# voice-card-controller-1_1.net
KiCad netlist of a schematic drawn in EAGLE
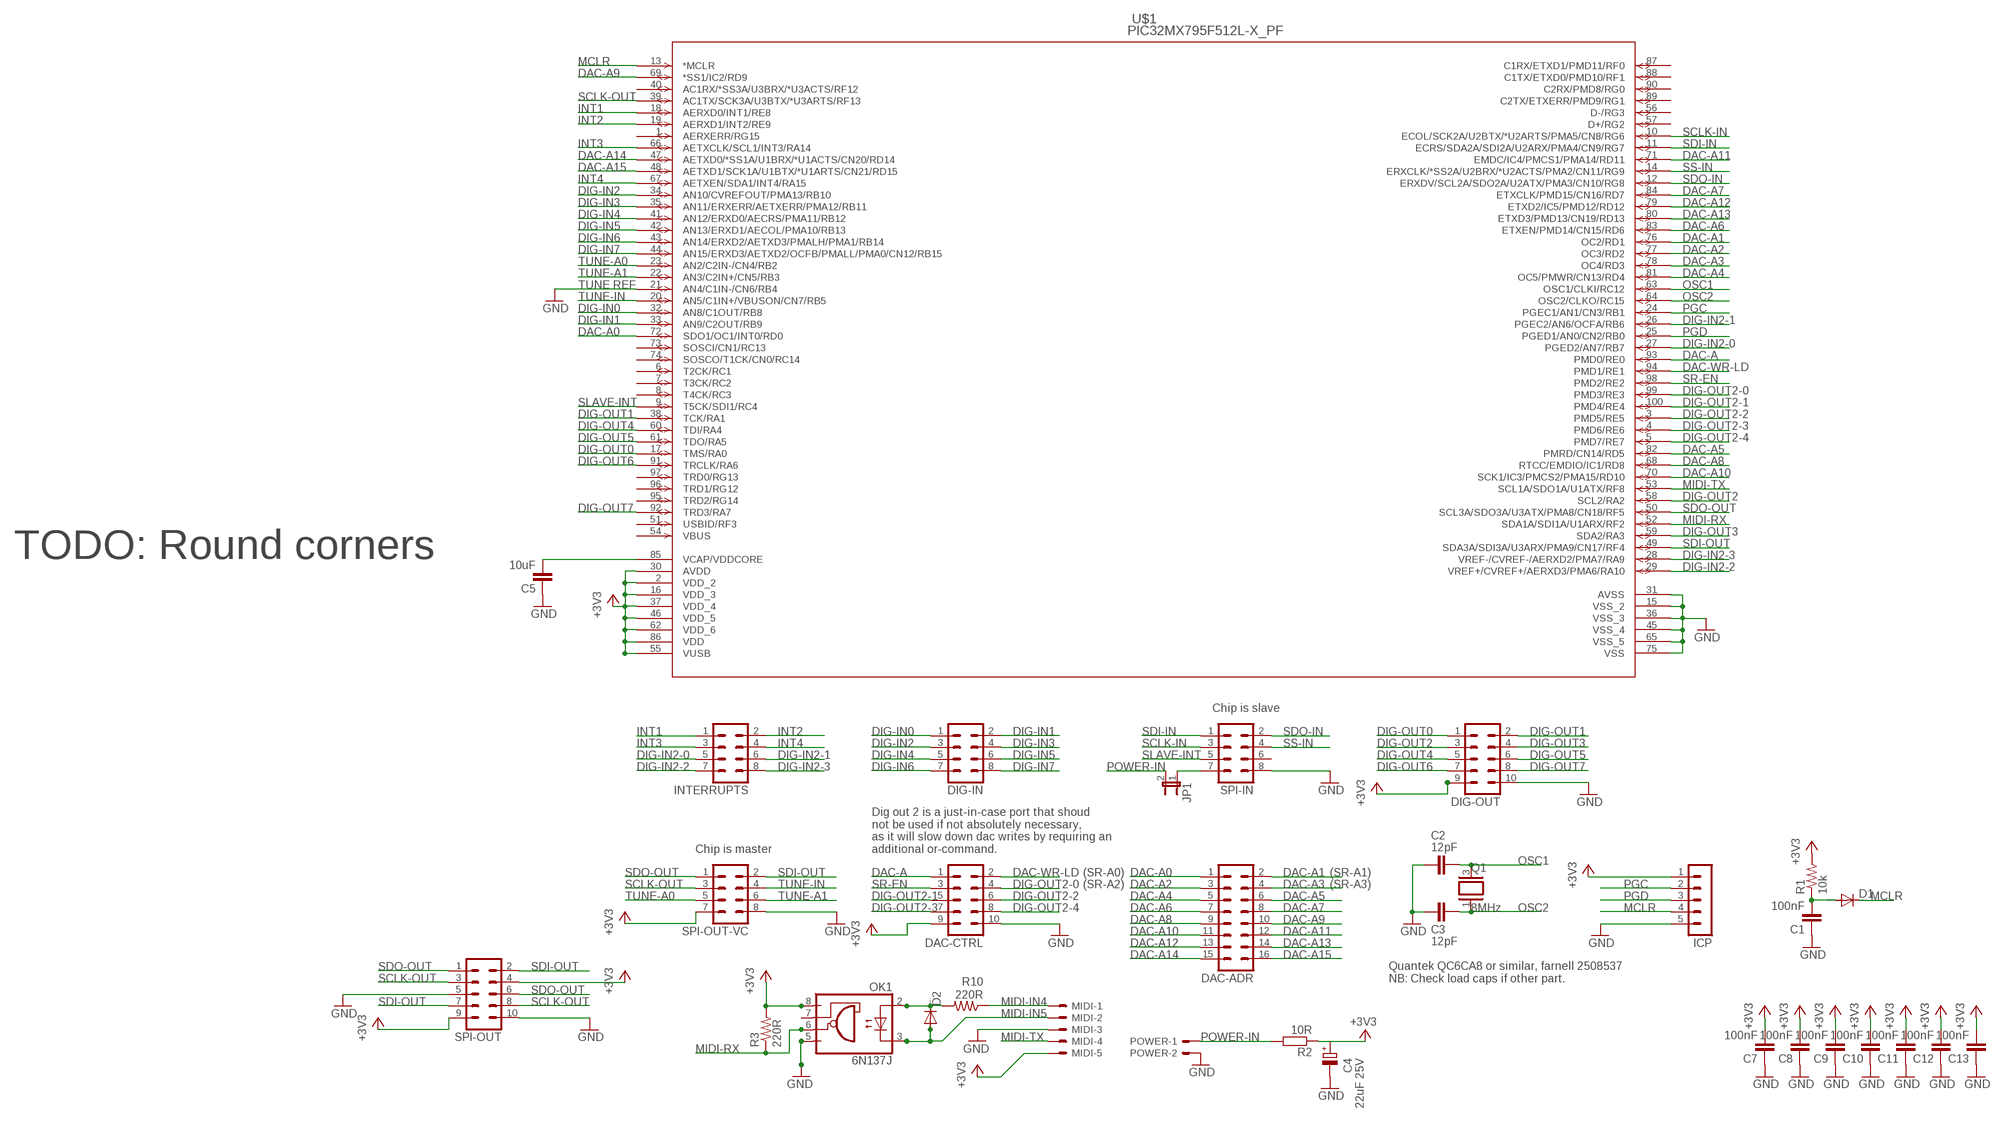
[diagram p0: schematic, sheet 1]

(export (version "E")
  (design (tool "Eeschema 10.0.6"))
  (components
    (comp (ref "C1")
      (value "100nF")
      (footprint "eagle-import:C0603")
      (libsource (lib "eagle-import") (part "C-EUC0603"))
    )
    (comp (ref "C2")
      (value "12pF")
      (footprint "eagle-import:C0603")
      (libsource (lib "eagle-import") (part "C-EUC0603"))
    )
    (comp (ref "C3")
      (value "12pF")
      (footprint "eagle-import:C0603")
      (libsource (lib "eagle-import") (part "C-EUC0603"))
    )
    (comp (ref "C4")
      (value "22uF 25V")
      (footprint "eagle-import:E2,5-5")
      (libsource (lib "eagle-import") (part "CPOL-EUE2.5-5"))
    )
    (comp (ref "C5")
      (value "10uF")
      (footprint "eagle-import:C0805")
      (libsource (lib "eagle-import") (part "C-EUC0805"))
    )
    (comp (ref "C7")
      (value "100nF")
      (footprint "eagle-import:C0603")
      (libsource (lib "eagle-import") (part "C-EUC0603"))
    )
    (comp (ref "C8")
      (value "100nF")
      (footprint "eagle-import:C0603")
      (libsource (lib "eagle-import") (part "C-EUC0603"))
    )
    (comp (ref "C9")
      (value "100nF")
      (footprint "eagle-import:C0603")
      (libsource (lib "eagle-import") (part "C-EUC0603"))
    )
    (comp (ref "C10")
      (value "100nF")
      (footprint "eagle-import:C0603")
      (libsource (lib "eagle-import") (part "C-EUC0603"))
    )
    (comp (ref "C11")
      (value "100nF")
      (footprint "eagle-import:C0603")
      (libsource (lib "eagle-import") (part "C-EUC0603"))
    )
    (comp (ref "C12")
      (value "100nF")
      (footprint "eagle-import:C0603")
      (libsource (lib "eagle-import") (part "C-EUC0603"))
    )
    (comp (ref "C13")
      (value "100nF")
      (footprint "eagle-import:C0603")
      (libsource (lib "eagle-import") (part "C-EUC0603"))
    )
    (comp (ref "D1")
      (value "DIODE-SOD80C")
      (footprint "eagle-import:SOD80C")
      (libsource (lib "eagle-import") (part "DIODE-SOD80C"))
    )
    (comp (ref "D2")
      (value "DIODE-SOD80C")
      (footprint "eagle-import:SOD80C")
      (libsource (lib "eagle-import") (part "DIODE-SOD80C"))
    )
    (comp (ref "DAC-ADR")
      (value "MA08-2J")
      (footprint "eagle-import:MA08-2J")
      (libsource (lib "eagle-import") (part "MA08-2J"))
    )
    (comp (ref "DAC-CTRL")
      (value "MA05-2J")
      (footprint "eagle-import:MA05-2J")
      (libsource (lib "eagle-import") (part "MA05-2J"))
    )
    (comp (ref "DIG-IN")
      (value "MA04-2J")
      (footprint "eagle-import:MA04-2J")
      (libsource (lib "eagle-import") (part "MA04-2J"))
    )
    (comp (ref "DIG-OUT")
      (value "MA05-2J")
      (footprint "eagle-import:MA05-2J")
      (libsource (lib "eagle-import") (part "MA05-2J"))
    )
    (comp (ref "ICP")
      (value "MA05-1")
      (footprint "eagle-import:MA05-1")
      (libsource (lib "eagle-import") (part "MA05-1"))
    )
    (comp (ref "INTERRUPTS")
      (value "MA04-2J")
      (footprint "eagle-import:MA04-2J")
      (libsource (lib "eagle-import") (part "MA04-2J"))
    )
    (comp (ref "JP1")
      (value "JP1E")
      (footprint "eagle-import:JP1")
      (libsource (lib "eagle-import") (part "JP1E"))
    )
    (comp (ref "MIDI")
      (value "22-23-2051")
      (footprint "eagle-import:22-23-2051")
      (fields (field (name "MF") "MOLEX"))
      (libsource (lib "eagle-import") (part "22-23-2051"))
    )
    (comp (ref "OK1")
      (value "6N137J")
      (footprint "eagle-import:DIL08-J")
      (libsource (lib "eagle-import") (part "6N137J"))
    )
    (comp (ref "POWER")
      (value "22-23-2021")
      (footprint "eagle-import:22-23-2021")
      (fields (field (name "MF") "MOLEX"))
      (libsource (lib "eagle-import") (part "22-23-2021"))
    )
    (comp (ref "Q1")
      (value "8MHz")
      (footprint "eagle-import:CTS406J")
      (libsource (lib "eagle-import") (part "XTAL-J"))
    )
    (comp (ref "R1")
      (value "10k")
      (footprint "eagle-import:R0805")
      (libsource (lib "eagle-import") (part "R-US_R0805"))
    )
    (comp (ref "R2")
      (value "10R")
      (footprint "eagle-import:0207_7")
      (libsource (lib "eagle-import") (part "R-EU_0207/7"))
    )
    (comp (ref "R3")
      (value "220R")
      (footprint "eagle-import:R0805")
      (libsource (lib "eagle-import") (part "R-US_R0805"))
    )
    (comp (ref "R10")
      (value "220R")
      (footprint "eagle-import:R0805")
      (libsource (lib "eagle-import") (part "R-US_R0805"))
    )
    (comp (ref "SPI-IN")
      (value "MA04-2J")
      (footprint "eagle-import:MA04-2J")
      (libsource (lib "eagle-import") (part "MA04-2J"))
    )
    (comp (ref "SPI-OUT")
      (value "MA05-2J")
      (footprint "eagle-import:MA05-2J")
      (libsource (lib "eagle-import") (part "MA05-2J"))
    )
    (comp (ref "SPI-OUT-VC")
      (value "MA04-2J")
      (footprint "eagle-import:MA04-2J")
      (libsource (lib "eagle-import") (part "MA04-2J"))
    )
    (comp (ref "U$1")
      (value "PIC32MX795F512L-X_PF")
      (footprint "eagle-import:TQFP100_14X14MC")
      (libsource (lib "eagle-import") (part "PIC32MX795F512L-X_PF"))
    )
  )
  (nets
    (net (code "1") (name "+3V3") (class "Default")
      (node (ref "C10") (pin "2") (pinfunction "2_2") (pintype "passive"))
      (node (ref "C11") (pin "2") (pinfunction "2_2") (pintype "passive"))
      (node (ref "C12") (pin "2") (pinfunction "2_2") (pintype "passive"))
      (node (ref "C13") (pin "2") (pinfunction "2_2") (pintype "passive"))
      (node (ref "C4") (pin "+") (pinfunction "+_+") (pintype "passive"))
      (node (ref "C7") (pin "2") (pinfunction "2_2") (pintype "passive"))
      (node (ref "C8") (pin "2") (pinfunction "2_2") (pintype "passive"))
      (node (ref "C9") (pin "2") (pinfunction "2_2") (pintype "passive"))
      (node (ref "DAC-CTRL") (pin "9") (pinfunction "9_9") (pintype "passive"))
      (node (ref "DIG-OUT") (pin "9") (pinfunction "9_9") (pintype "passive"))
      (node (ref "ICP") (pin "1") (pinfunction "1_1") (pintype "passive"))
      (node (ref "MIDI") (pin "5") (pinfunction "S_5") (pintype "passive"))
      (node (ref "OK1") (pin "8") (pinfunction "VCC_8") (pintype "passive"))
      (node (ref "R1") (pin "2") (pinfunction "2_2") (pintype "passive"))
      (node (ref "R2") (pin "1") (pinfunction "1_1") (pintype "passive"))
      (node (ref "R3") (pin "2") (pinfunction "2_2") (pintype "passive"))
      (node (ref "SPI-OUT") (pin "4") (pinfunction "4_4") (pintype "passive"))
      (node (ref "SPI-OUT") (pin "9") (pinfunction "9_9") (pintype "passive"))
      (node (ref "SPI-OUT-VC") (pin "7") (pinfunction "7_7") (pintype "passive"))
      (node (ref "U$1") (pin "16") (pinfunction "VDD_3_16") (pintype "power_in"))
      (node (ref "U$1") (pin "2") (pinfunction "VDD_2_2") (pintype "power_in"))
      (node (ref "U$1") (pin "30") (pinfunction "AVDD_30") (pintype "power_in"))
      (node (ref "U$1") (pin "37") (pinfunction "VDD_4_37") (pintype "power_in"))
      (node (ref "U$1") (pin "46") (pinfunction "VDD_5_46") (pintype "power_in"))
      (node (ref "U$1") (pin "55") (pinfunction "VUSB_55") (pintype "power_in"))
      (node (ref "U$1") (pin "62") (pinfunction "VDD_6_62") (pintype "power_in"))
      (node (ref "U$1") (pin "86") (pinfunction "VDD_86") (pintype "power_in"))
    )
    (net (code "2") (name "/DAC-A") (class "Default")
      (node (ref "DAC-CTRL") (pin "1") (pinfunction "1_1") (pintype "passive"))
      (node (ref "U$1") (pin "93") (pinfunction "PMD0/RE0_93") (pintype "bidirectional"))
    )
    (net (code "3") (name "/DAC-A0") (class "Default")
      (node (ref "DAC-ADR") (pin "1") (pinfunction "1_1") (pintype "passive"))
      (node (ref "U$1") (pin "72") (pinfunction "SDO1/OC1/INT0/RD0_72") (pintype "bidirectional"))
    )
    (net (code "4") (name "/DAC-A1") (class "Default")
      (node (ref "DAC-ADR") (pin "2") (pinfunction "2_2") (pintype "passive"))
      (node (ref "U$1") (pin "76") (pinfunction "OC2/RD1_76") (pintype "bidirectional"))
    )
    (net (code "5") (name "/DAC-A2") (class "Default")
      (node (ref "DAC-ADR") (pin "3") (pinfunction "3_3") (pintype "passive"))
      (node (ref "U$1") (pin "77") (pinfunction "OC3/RD2_77") (pintype "bidirectional"))
    )
    (net (code "6") (name "/DAC-A3") (class "Default")
      (node (ref "DAC-ADR") (pin "4") (pinfunction "4_4") (pintype "passive"))
      (node (ref "U$1") (pin "78") (pinfunction "OC4/RD3_78") (pintype "bidirectional"))
    )
    (net (code "7") (name "/DAC-A4") (class "Default")
      (node (ref "DAC-ADR") (pin "5") (pinfunction "5_5") (pintype "passive"))
      (node (ref "U$1") (pin "81") (pinfunction "OC5/PMWR/CN13/RD4_81") (pintype "bidirectional"))
    )
    (net (code "8") (name "/DAC-A5") (class "Default")
      (node (ref "DAC-ADR") (pin "6") (pinfunction "6_6") (pintype "passive"))
      (node (ref "U$1") (pin "82") (pinfunction "PMRD/CN14/RD5_82") (pintype "bidirectional"))
    )
    (net (code "9") (name "/DAC-A6") (class "Default")
      (node (ref "DAC-ADR") (pin "7") (pinfunction "7_7") (pintype "passive"))
      (node (ref "U$1") (pin "83") (pinfunction "ETXEN/PMD14/CN15/RD6_83") (pintype "bidirectional"))
    )
    (net (code "10") (name "/DAC-A7") (class "Default")
      (node (ref "DAC-ADR") (pin "8") (pinfunction "8_8") (pintype "passive"))
      (node (ref "U$1") (pin "84") (pinfunction "ETXCLK/PMD15/CN16/RD7_84") (pintype "bidirectional"))
    )
    (net (code "11") (name "/DAC-A8") (class "Default")
      (node (ref "DAC-ADR") (pin "9") (pinfunction "9_9") (pintype "passive"))
      (node (ref "U$1") (pin "68") (pinfunction "RTCC/EMDIO/IC1/RD8_68") (pintype "bidirectional"))
    )
    (net (code "12") (name "/DAC-A9") (class "Default")
      (node (ref "DAC-ADR") (pin "10") (pinfunction "10_10") (pintype "passive"))
      (node (ref "U$1") (pin "69") (pinfunction "*SS1/IC2/RD9_69") (pintype "bidirectional"))
    )
    (net (code "13") (name "/DAC-A10") (class "Default")
      (node (ref "DAC-ADR") (pin "11") (pinfunction "11_11") (pintype "passive"))
      (node (ref "U$1") (pin "70") (pinfunction "SCK1/IC3/PMCS2/PMA15/RD10_70") (pintype "bidirectional"))
    )
    (net (code "14") (name "/DAC-A11") (class "Default")
      (node (ref "DAC-ADR") (pin "12") (pinfunction "12_12") (pintype "passive"))
      (node (ref "U$1") (pin "71") (pinfunction "EMDC/IC4/PMCS1/PMA14/RD11_71") (pintype "bidirectional"))
    )
    (net (code "15") (name "/DAC-A12") (class "Default")
      (node (ref "DAC-ADR") (pin "13") (pinfunction "13_13") (pintype "passive"))
      (node (ref "U$1") (pin "79") (pinfunction "ETXD2/IC5/PMD12/RD12_79") (pintype "bidirectional"))
    )
    (net (code "16") (name "/DAC-A13") (class "Default")
      (node (ref "DAC-ADR") (pin "14") (pinfunction "14_14") (pintype "passive"))
      (node (ref "U$1") (pin "80") (pinfunction "ETXD3/PMD13/CN19/RD13_80") (pintype "bidirectional"))
    )
    (net (code "17") (name "/DAC-A14") (class "Default")
      (node (ref "DAC-ADR") (pin "15") (pinfunction "15_15") (pintype "passive"))
      (node (ref "U$1") (pin "47") (pinfunction "AETXD0/*SS1A/U1BRX/*U1ACTS/CN20/RD14_47") (pintype "bidirectional"))
    )
    (net (code "18") (name "/DAC-A15") (class "Default")
      (node (ref "DAC-ADR") (pin "16") (pinfunction "16_16") (pintype "passive"))
      (node (ref "U$1") (pin "48") (pinfunction "AETXD1/SCK1A/U1BTX/*U1ARTS/CN21/RD15_48") (pintype "bidirectional"))
    )
    (net (code "19") (name "/DAC-WR-LD") (class "Default")
      (node (ref "DAC-CTRL") (pin "2") (pinfunction "2_2") (pintype "passive"))
      (node (ref "U$1") (pin "94") (pinfunction "PMD1/RE1_94") (pintype "bidirectional"))
    )
    (net (code "20") (name "/DIG-IN0") (class "Default")
      (node (ref "DIG-IN") (pin "1") (pinfunction "1_1") (pintype "passive"))
      (node (ref "U$1") (pin "32") (pinfunction "AN8/C1OUT/RB8_32") (pintype "bidirectional"))
    )
    (net (code "21") (name "/DIG-IN1") (class "Default")
      (node (ref "DIG-IN") (pin "2") (pinfunction "2_2") (pintype "passive"))
      (node (ref "U$1") (pin "33") (pinfunction "AN9/C2OUT/RB9_33") (pintype "bidirectional"))
    )
    (net (code "22") (name "/DIG-IN2") (class "Default")
      (node (ref "DIG-IN") (pin "3") (pinfunction "3_3") (pintype "passive"))
      (node (ref "U$1") (pin "34") (pinfunction "AN10/CVREFOUT/PMA13/RB10_34") (pintype "bidirectional"))
    )
    (net (code "23") (name "/DIG-IN2-0") (class "Default")
      (node (ref "INTERRUPTS") (pin "5") (pinfunction "5_5") (pintype "passive"))
      (node (ref "U$1") (pin "27") (pinfunction "PGED2/AN7/RB7_27") (pintype "bidirectional"))
    )
    (net (code "24") (name "/DIG-IN2-1") (class "Default")
      (node (ref "INTERRUPTS") (pin "6") (pinfunction "6_6") (pintype "passive"))
      (node (ref "U$1") (pin "26") (pinfunction "PGEC2/AN6/OCFA/RB6_26") (pintype "bidirectional"))
    )
    (net (code "25") (name "/DIG-IN2-2") (class "Default")
      (node (ref "INTERRUPTS") (pin "7") (pinfunction "7_7") (pintype "passive"))
      (node (ref "U$1") (pin "29") (pinfunction "VREF+/CVREF+/AERXD3/PMA6/RA10_29") (pintype "bidirectional"))
    )
    (net (code "26") (name "/DIG-IN2-3") (class "Default")
      (node (ref "INTERRUPTS") (pin "8") (pinfunction "8_8") (pintype "passive"))
      (node (ref "U$1") (pin "28") (pinfunction "VREF-/CVREF-/AERXD2/PMA7/RA9_28") (pintype "bidirectional"))
    )
    (net (code "27") (name "/DIG-IN3") (class "Default")
      (node (ref "DIG-IN") (pin "4") (pinfunction "4_4") (pintype "passive"))
      (node (ref "U$1") (pin "35") (pinfunction "AN11/ERXERR/AETXERR/PMA12/RB11_35") (pintype "bidirectional"))
    )
    (net (code "28") (name "/DIG-IN4") (class "Default")
      (node (ref "DIG-IN") (pin "5") (pinfunction "5_5") (pintype "passive"))
      (node (ref "U$1") (pin "41") (pinfunction "AN12/ERXD0/AECRS/PMA11/RB12_41") (pintype "bidirectional"))
    )
    (net (code "29") (name "/DIG-IN5") (class "Default")
      (node (ref "DIG-IN") (pin "6") (pinfunction "6_6") (pintype "passive"))
      (node (ref "U$1") (pin "42") (pinfunction "AN13/ERXD1/AECOL/PMA10/RB13_42") (pintype "bidirectional"))
    )
    (net (code "30") (name "/DIG-IN6") (class "Default")
      (node (ref "DIG-IN") (pin "7") (pinfunction "7_7") (pintype "passive"))
      (node (ref "U$1") (pin "43") (pinfunction "AN14/ERXD2/AETXD3/PMALH/PMA1/RB14_43") (pintype "bidirectional"))
    )
    (net (code "31") (name "/DIG-IN7") (class "Default")
      (node (ref "DIG-IN") (pin "8") (pinfunction "8_8") (pintype "passive"))
      (node (ref "U$1") (pin "44") (pinfunction "AN15/ERXD3/AETXD2/OCFB/PMALL/PMA0/CN12/RB15_44") (pintype "bidirectional"))
    )
    (net (code "32") (name "/DIG-OUT0") (class "Default")
      (node (ref "DIG-OUT") (pin "1") (pinfunction "1_1") (pintype "passive"))
      (node (ref "U$1") (pin "17") (pinfunction "TMS/RA0_17") (pintype "bidirectional"))
    )
    (net (code "33") (name "/DIG-OUT1") (class "Default")
      (node (ref "DIG-OUT") (pin "2") (pinfunction "2_2") (pintype "passive"))
      (node (ref "U$1") (pin "38") (pinfunction "TCK/RA1_38") (pintype "bidirectional"))
    )
    (net (code "34") (name "/DIG-OUT2") (class "Default")
      (node (ref "DIG-OUT") (pin "3") (pinfunction "3_3") (pintype "passive"))
      (node (ref "U$1") (pin "58") (pinfunction "SCL2/RA2_58") (pintype "bidirectional"))
    )
    (net (code "35") (name "/DIG-OUT2-0") (class "Default")
      (node (ref "DAC-CTRL") (pin "4") (pinfunction "4_4") (pintype "passive"))
      (node (ref "U$1") (pin "99") (pinfunction "PMD3/RE3_99") (pintype "bidirectional"))
    )
    (net (code "36") (name "/DIG-OUT2-1") (class "Default")
      (node (ref "DAC-CTRL") (pin "5") (pinfunction "5_5") (pintype "passive"))
      (node (ref "U$1") (pin "100") (pinfunction "PMD4/RE4_100") (pintype "bidirectional"))
    )
    (net (code "37") (name "/DIG-OUT2-2") (class "Default")
      (node (ref "DAC-CTRL") (pin "6") (pinfunction "6_6") (pintype "passive"))
      (node (ref "U$1") (pin "3") (pinfunction "PMD5/RE5_3") (pintype "bidirectional"))
    )
    (net (code "38") (name "/DIG-OUT2-3") (class "Default")
      (node (ref "DAC-CTRL") (pin "7") (pinfunction "7_7") (pintype "passive"))
      (node (ref "U$1") (pin "4") (pinfunction "PMD6/RE6_4") (pintype "bidirectional"))
    )
    (net (code "39") (name "/DIG-OUT2-4") (class "Default")
      (node (ref "DAC-CTRL") (pin "8") (pinfunction "8_8") (pintype "passive"))
      (node (ref "U$1") (pin "5") (pinfunction "PMD7/RE7_5") (pintype "bidirectional"))
    )
    (net (code "40") (name "/DIG-OUT3") (class "Default")
      (node (ref "DIG-OUT") (pin "4") (pinfunction "4_4") (pintype "passive"))
      (node (ref "U$1") (pin "59") (pinfunction "SDA2/RA3_59") (pintype "bidirectional"))
    )
    (net (code "41") (name "/DIG-OUT4") (class "Default")
      (node (ref "DIG-OUT") (pin "5") (pinfunction "5_5") (pintype "passive"))
      (node (ref "U$1") (pin "60") (pinfunction "TDI/RA4_60") (pintype "bidirectional"))
    )
    (net (code "42") (name "/DIG-OUT5") (class "Default")
      (node (ref "DIG-OUT") (pin "6") (pinfunction "6_6") (pintype "passive"))
      (node (ref "U$1") (pin "61") (pinfunction "TDO/RA5_61") (pintype "bidirectional"))
    )
    (net (code "43") (name "/DIG-OUT6") (class "Default")
      (node (ref "DIG-OUT") (pin "7") (pinfunction "7_7") (pintype "passive"))
      (node (ref "U$1") (pin "91") (pinfunction "TRCLK/RA6_91") (pintype "bidirectional"))
    )
    (net (code "44") (name "/DIG-OUT7") (class "Default")
      (node (ref "DIG-OUT") (pin "8") (pinfunction "8_8") (pintype "passive"))
      (node (ref "U$1") (pin "92") (pinfunction "TRD3/RA7_92") (pintype "bidirectional"))
    )
    (net (code "45") (name "/INT1") (class "Default")
      (node (ref "INTERRUPTS") (pin "1") (pinfunction "1_1") (pintype "passive"))
      (node (ref "U$1") (pin "18") (pinfunction "AERXD0/INT1/RE8_18") (pintype "bidirectional"))
    )
    (net (code "46") (name "/INT2") (class "Default")
      (node (ref "INTERRUPTS") (pin "2") (pinfunction "2_2") (pintype "passive"))
      (node (ref "U$1") (pin "19") (pinfunction "AERXD1/INT2/RE9_19") (pintype "bidirectional"))
    )
    (net (code "47") (name "/INT3") (class "Default")
      (node (ref "INTERRUPTS") (pin "3") (pinfunction "3_3") (pintype "passive"))
      (node (ref "U$1") (pin "66") (pinfunction "AETXCLK/SCL1/INT3/RA14_66") (pintype "bidirectional"))
    )
    (net (code "48") (name "/INT4") (class "Default")
      (node (ref "INTERRUPTS") (pin "4") (pinfunction "4_4") (pintype "passive"))
      (node (ref "U$1") (pin "67") (pinfunction "AETXEN/SDA1/INT4/RA15_67") (pintype "bidirectional"))
    )
    (net (code "49") (name "/MCLR") (class "Default")
      (node (ref "D1") (pin "C") (pinfunction "C_C") (pintype "passive"))
      (node (ref "ICP") (pin "4") (pinfunction "4_4") (pintype "passive"))
      (node (ref "U$1") (pin "13") (pinfunction "*MCLR_13") (pintype "input"))
    )
    (net (code "50") (name "/MIDI-IN4") (class "Default")
      (node (ref "MIDI") (pin "1") (pinfunction "S_1") (pintype "passive"))
      (node (ref "R10") (pin "1") (pinfunction "1_1") (pintype "passive"))
    )
    (net (code "51") (name "/MIDI-IN5") (class "Default")
      (node (ref "D2") (pin "A") (pinfunction "A_A") (pintype "passive"))
      (node (ref "MIDI") (pin "2") (pinfunction "S_2") (pintype "passive"))
      (node (ref "OK1") (pin "3") (pinfunction "C_3") (pintype "passive"))
    )
    (net (code "52") (name "/MIDI-RX") (class "Default")
      (node (ref "OK1") (pin "6") (pinfunction "VO_6") (pintype "passive"))
      (node (ref "R3") (pin "1") (pinfunction "1_1") (pintype "passive"))
      (node (ref "U$1") (pin "52") (pinfunction "SDA1A/SDI1A/U1ARX/RF2_52") (pintype "bidirectional"))
    )
    (net (code "53") (name "/MIDI-TX") (class "Default")
      (node (ref "MIDI") (pin "4") (pinfunction "S_4") (pintype "passive"))
      (node (ref "U$1") (pin "53") (pinfunction "SCL1A/SDO1A/U1ATX/RF8_53") (pintype "bidirectional"))
    )
    (net (code "54") (name "/OSC1") (class "Default")
      (node (ref "C2") (pin "1") (pinfunction "1_1") (pintype "passive"))
      (node (ref "Q1") (pin "3") (pinfunction "2_3") (pintype "passive"))
      (node (ref "U$1") (pin "63") (pinfunction "OSC1/CLKI/RC12_63") (pintype "bidirectional"))
    )
    (net (code "55") (name "/OSC2") (class "Default")
      (node (ref "C3") (pin "1") (pinfunction "1_1") (pintype "passive"))
      (node (ref "Q1") (pin "1") (pinfunction "1_1") (pintype "passive"))
      (node (ref "U$1") (pin "64") (pinfunction "OSC2/CLKO/RC15_64") (pintype "bidirectional"))
    )
    (net (code "56") (name "/PGC") (class "Default")
      (node (ref "ICP") (pin "2") (pinfunction "2_2") (pintype "passive"))
      (node (ref "U$1") (pin "24") (pinfunction "PGEC1/AN1/CN3/RB1_24") (pintype "bidirectional"))
    )
    (net (code "57") (name "/PGD") (class "Default")
      (node (ref "ICP") (pin "3") (pinfunction "3_3") (pintype "passive"))
      (node (ref "U$1") (pin "25") (pinfunction "PGED1/AN0/CN2/RB0_25") (pintype "bidirectional"))
    )
    (net (code "58") (name "/POWER-IN") (class "Default")
      (node (ref "JP1") (pin "2") (pinfunction "2_2") (pintype "passive"))
      (node (ref "POWER") (pin "1") (pinfunction "S_1") (pintype "passive"))
      (node (ref "R2") (pin "2") (pinfunction "2_2") (pintype "passive"))
    )
    (net (code "59") (name "/SCLK-IN") (class "Default")
      (node (ref "SPI-IN") (pin "3") (pinfunction "3_3") (pintype "passive"))
      (node (ref "U$1") (pin "10") (pinfunction "ECOL/SCK2A/U2BTX/*U2ARTS/PMA5/CN8/RG6_10") (pintype "bidirectional"))
    )
    (net (code "60") (name "/SCLK-OUT") (class "Default")
      (node (ref "SPI-OUT") (pin "3") (pinfunction "3_3") (pintype "passive"))
      (node (ref "SPI-OUT") (pin "8") (pinfunction "8_8") (pintype "passive"))
      (node (ref "SPI-OUT-VC") (pin "3") (pinfunction "3_3") (pintype "passive"))
      (node (ref "U$1") (pin "39") (pinfunction "AC1TX/SCK3A/U3BTX/*U3ARTS/RF13_39") (pintype "bidirectional"))
    )
    (net (code "61") (name "/SDI-IN") (class "Default")
      (node (ref "SPI-IN") (pin "1") (pinfunction "1_1") (pintype "passive"))
      (node (ref "U$1") (pin "11") (pinfunction "ECRS/SDA2A/SDI2A/U2ARX/PMA4/CN9/RG7_11") (pintype "bidirectional"))
    )
    (net (code "62") (name "/SDI-OUT") (class "Default")
      (node (ref "SPI-OUT") (pin "2") (pinfunction "2_2") (pintype "passive"))
      (node (ref "SPI-OUT") (pin "7") (pinfunction "7_7") (pintype "passive"))
      (node (ref "SPI-OUT-VC") (pin "2") (pinfunction "2_2") (pintype "passive"))
      (node (ref "U$1") (pin "49") (pinfunction "SDA3A/SDI3A/U3ARX/PMA9/CN17/RF4_49") (pintype "bidirectional"))
    )
    (net (code "63") (name "/SDO-IN") (class "Default")
      (node (ref "SPI-IN") (pin "2") (pinfunction "2_2") (pintype "passive"))
      (node (ref "U$1") (pin "12") (pinfunction "ERXDV/SCL2A/SDO2A/U2ATX/PMA3/CN10/RG8_12") (pintype "bidirectional"))
    )
    (net (code "64") (name "/SDO-OUT") (class "Default")
      (node (ref "SPI-OUT") (pin "1") (pinfunction "1_1") (pintype "passive"))
      (node (ref "SPI-OUT") (pin "6") (pinfunction "6_6") (pintype "passive"))
      (node (ref "SPI-OUT-VC") (pin "1") (pinfunction "1_1") (pintype "passive"))
      (node (ref "U$1") (pin "50") (pinfunction "SCL3A/SDO3A/U3ATX/PMA8/CN18/RF5_50") (pintype "bidirectional"))
    )
    (net (code "65") (name "/SLAVE-INT") (class "Default")
      (node (ref "SPI-IN") (pin "5") (pinfunction "5_5") (pintype "passive"))
      (node (ref "U$1") (pin "9") (pinfunction "T5CK/SDI1/RC4_9") (pintype "bidirectional"))
    )
    (net (code "66") (name "/SR-EN") (class "Default")
      (node (ref "DAC-CTRL") (pin "3") (pinfunction "3_3") (pintype "passive"))
      (node (ref "U$1") (pin "98") (pinfunction "PMD2/RE2_98") (pintype "bidirectional"))
    )
    (net (code "67") (name "/SS-IN") (class "Default")
      (node (ref "SPI-IN") (pin "4") (pinfunction "4_4") (pintype "passive"))
      (node (ref "U$1") (pin "14") (pinfunction "ERXCLK/*SS2A/U2BRX/*U2ACTS/PMA2/CN11/RG9_14") (pintype "bidirectional"))
    )
    (net (code "68") (name "/TUNE-A0") (class "Default")
      (node (ref "SPI-OUT-VC") (pin "5") (pinfunction "5_5") (pintype "passive"))
      (node (ref "U$1") (pin "23") (pinfunction "AN2/C2IN-/CN4/RB2_23") (pintype "bidirectional"))
    )
    (net (code "69") (name "/TUNE-A1") (class "Default")
      (node (ref "SPI-OUT-VC") (pin "6") (pinfunction "6_6") (pintype "passive"))
      (node (ref "U$1") (pin "22") (pinfunction "AN3/C2IN+/CN5/RB3_22") (pintype "bidirectional"))
    )
    (net (code "70") (name "/TUNE-IN") (class "Default")
      (node (ref "SPI-OUT-VC") (pin "4") (pinfunction "4_4") (pintype "passive"))
      (node (ref "U$1") (pin "20") (pinfunction "AN5/C1IN+/VBUSON/CN7/RB5_20") (pintype "bidirectional"))
    )
    (net (code "71") (name "GND") (class "Default")
      (node (ref "C1") (pin "1") (pinfunction "1_1") (pintype "passive"))
      (node (ref "C10") (pin "1") (pinfunction "1_1") (pintype "passive"))
      (node (ref "C11") (pin "1") (pinfunction "1_1") (pintype "passive"))
      (node (ref "C12") (pin "1") (pinfunction "1_1") (pintype "passive"))
      (node (ref "C13") (pin "1") (pinfunction "1_1") (pintype "passive"))
      (node (ref "C2") (pin "2") (pinfunction "2_2") (pintype "passive"))
      (node (ref "C3") (pin "2") (pinfunction "2_2") (pintype "passive"))
      (node (ref "C4") (pin "-") (pinfunction "-_-") (pintype "passive"))
      (node (ref "C5") (pin "1") (pinfunction "1_1") (pintype "passive"))
      (node (ref "C7") (pin "1") (pinfunction "1_1") (pintype "passive"))
      (node (ref "C8") (pin "1") (pinfunction "1_1") (pintype "passive"))
      (node (ref "C9") (pin "1") (pinfunction "1_1") (pintype "passive"))
      (node (ref "DAC-CTRL") (pin "10") (pinfunction "10_10") (pintype "passive"))
      (node (ref "DIG-OUT") (pin "10") (pinfunction "10_10") (pintype "passive"))
      (node (ref "ICP") (pin "5") (pinfunction "5_5") (pintype "passive"))
      (node (ref "MIDI") (pin "3") (pinfunction "S_3") (pintype "passive"))
      (node (ref "OK1") (pin "5") (pinfunction "GND_5") (pintype "passive"))
      (node (ref "POWER") (pin "2") (pinfunction "S_2") (pintype "passive"))
      (node (ref "SPI-IN") (pin "8") (pinfunction "8_8") (pintype "passive"))
      (node (ref "SPI-OUT") (pin "10") (pinfunction "10_10") (pintype "passive"))
      (node (ref "SPI-OUT") (pin "5") (pinfunction "5_5") (pintype "passive"))
      (node (ref "SPI-OUT-VC") (pin "8") (pinfunction "8_8") (pintype "passive"))
      (node (ref "U$1") (pin "15") (pinfunction "VSS_2_15") (pintype "power_in"))
      (node (ref "U$1") (pin "21") (pinfunction "AN4/C1IN-/CN6/RB4_21") (pintype "bidirectional"))
      (node (ref "U$1") (pin "31") (pinfunction "AVSS_31") (pintype "power_in"))
      (node (ref "U$1") (pin "36") (pinfunction "VSS_3_36") (pintype "power_in"))
      (node (ref "U$1") (pin "45") (pinfunction "VSS_4_45") (pintype "power_in"))
      (node (ref "U$1") (pin "65") (pinfunction "VSS_5_65") (pintype "power_in"))
      (node (ref "U$1") (pin "75") (pinfunction "VSS_75") (pintype "power_in"))
    )
    (net (code "72") (name "Net-(C1-Pad2)") (class "Default")
      (node (ref "C1") (pin "2") (pinfunction "2_2") (pintype "passive"))
      (node (ref "D1") (pin "A") (pinfunction "A_A") (pintype "passive"))
      (node (ref "R1") (pin "1") (pinfunction "1_1") (pintype "passive"))
    )
    (net (code "73") (name "Net-(JP1-Pad1)") (class "Default")
      (node (ref "JP1") (pin "1") (pinfunction "1_1") (pintype "passive"))
      (node (ref "SPI-IN") (pin "7") (pinfunction "7_7") (pintype "passive"))
    )
    (net (code "74") (name "Net-(OK1-A)") (class "Default")
      (node (ref "D2") (pin "C") (pinfunction "C_C") (pintype "passive"))
      (node (ref "OK1") (pin "2") (pinfunction "A_2") (pintype "passive"))
      (node (ref "R10") (pin "2") (pinfunction "2_2") (pintype "passive"))
    )
    (net (code "75") (name "Net-(U$1-VCAP{slash}VDDCORE)") (class "Default")
      (node (ref "C5") (pin "2") (pinfunction "2_2") (pintype "passive"))
      (node (ref "U$1") (pin "85") (pinfunction "VCAP/VDDCORE_85") (pintype "power_in"))
    )
    (net (code "76") (name "unconnected-(OK1-VE-Pad7)") (class "Default")
      (node (ref "OK1") (pin "7") (pinfunction "VE_7") (pintype "passive"))
    )
    (net (code "77") (name "unconnected-(SPI-IN-Pad6)") (class "Default")
      (node (ref "SPI-IN") (pin "6") (pinfunction "6_6") (pintype "passive"))
    )
    (net (code "78") (name "unconnected-(U$1-AC1RX{slash}*SS3A{slash}U3BRX{slash}*U3ACTS{slash}RF12-Pad40)") (class "Default")
      (node (ref "U$1") (pin "40") (pinfunction "AC1RX/*SS3A/U3BRX/*U3ACTS/RF12_40") (pintype "bidirectional"))
    )
    (net (code "79") (name "unconnected-(U$1-AERXERR{slash}RG15-Pad1)") (class "Default")
      (node (ref "U$1") (pin "1") (pinfunction "AERXERR/RG15_1") (pintype "bidirectional"))
    )
    (net (code "80") (name "unconnected-(U$1-C1RX{slash}ETXD1{slash}PMD11{slash}RF0-Pad87)") (class "Default")
      (node (ref "U$1") (pin "87") (pinfunction "C1RX/ETXD1/PMD11/RF0_87") (pintype "bidirectional"))
    )
    (net (code "81") (name "unconnected-(U$1-C1TX{slash}ETXD0{slash}PMD10{slash}RF1-Pad88)") (class "Default")
      (node (ref "U$1") (pin "88") (pinfunction "C1TX/ETXD0/PMD10/RF1_88") (pintype "bidirectional"))
    )
    (net (code "82") (name "unconnected-(U$1-C2RX{slash}PMD8{slash}RG0-Pad90)") (class "Default")
      (node (ref "U$1") (pin "90") (pinfunction "C2RX/PMD8/RG0_90") (pintype "bidirectional"))
    )
    (net (code "83") (name "unconnected-(U$1-C2TX{slash}ETXERR{slash}PMD9{slash}RG1-Pad89)") (class "Default")
      (node (ref "U$1") (pin "89") (pinfunction "C2TX/ETXERR/PMD9/RG1_89") (pintype "bidirectional"))
    )
    (net (code "84") (name "unconnected-(U$1-D+{slash}RG2-Pad57)") (class "Default")
      (node (ref "U$1") (pin "57") (pinfunction "D+/RG2_57") (pintype "bidirectional"))
    )
    (net (code "85") (name "unconnected-(U$1-D-{slash}RG3-Pad56)") (class "Default")
      (node (ref "U$1") (pin "56") (pinfunction "D-/RG3_56") (pintype "bidirectional"))
    )
    (net (code "86") (name "unconnected-(U$1-SOSCI{slash}CN1{slash}RC13-Pad73)") (class "Default")
      (node (ref "U$1") (pin "73") (pinfunction "SOSCI/CN1/RC13_73") (pintype "bidirectional"))
    )
    (net (code "87") (name "unconnected-(U$1-SOSCO{slash}T1CK{slash}CN0{slash}RC14-Pad74)") (class "Default")
      (node (ref "U$1") (pin "74") (pinfunction "SOSCO/T1CK/CN0/RC14_74") (pintype "bidirectional"))
    )
    (net (code "88") (name "unconnected-(U$1-T2CK{slash}RC1-Pad6)") (class "Default")
      (node (ref "U$1") (pin "6") (pinfunction "T2CK/RC1_6") (pintype "bidirectional"))
    )
    (net (code "89") (name "unconnected-(U$1-T3CK{slash}RC2-Pad7)") (class "Default")
      (node (ref "U$1") (pin "7") (pinfunction "T3CK/RC2_7") (pintype "bidirectional"))
    )
    (net (code "90") (name "unconnected-(U$1-T4CK{slash}RC3-Pad8)") (class "Default")
      (node (ref "U$1") (pin "8") (pinfunction "T4CK/RC3_8") (pintype "bidirectional"))
    )
    (net (code "91") (name "unconnected-(U$1-TRD0{slash}RG13-Pad97)") (class "Default")
      (node (ref "U$1") (pin "97") (pinfunction "TRD0/RG13_97") (pintype "bidirectional"))
    )
    (net (code "92") (name "unconnected-(U$1-TRD1{slash}RG12-Pad96)") (class "Default")
      (node (ref "U$1") (pin "96") (pinfunction "TRD1/RG12_96") (pintype "bidirectional"))
    )
    (net (code "93") (name "unconnected-(U$1-TRD2{slash}RG14-Pad95)") (class "Default")
      (node (ref "U$1") (pin "95") (pinfunction "TRD2/RG14_95") (pintype "bidirectional"))
    )
    (net (code "94") (name "unconnected-(U$1-USBID{slash}RF3-Pad51)") (class "Default")
      (node (ref "U$1") (pin "51") (pinfunction "USBID/RF3_51") (pintype "bidirectional"))
    )
    (net (code "95") (name "unconnected-(U$1-VBUS-Pad54)") (class "Default")
      (node (ref "U$1") (pin "54") (pinfunction "VBUS_54") (pintype "input"))
    )
  )
)
